# Meadowlark_Mini_Schematic_v30.net
KiCad netlist of a schematic drawn in EAGLE
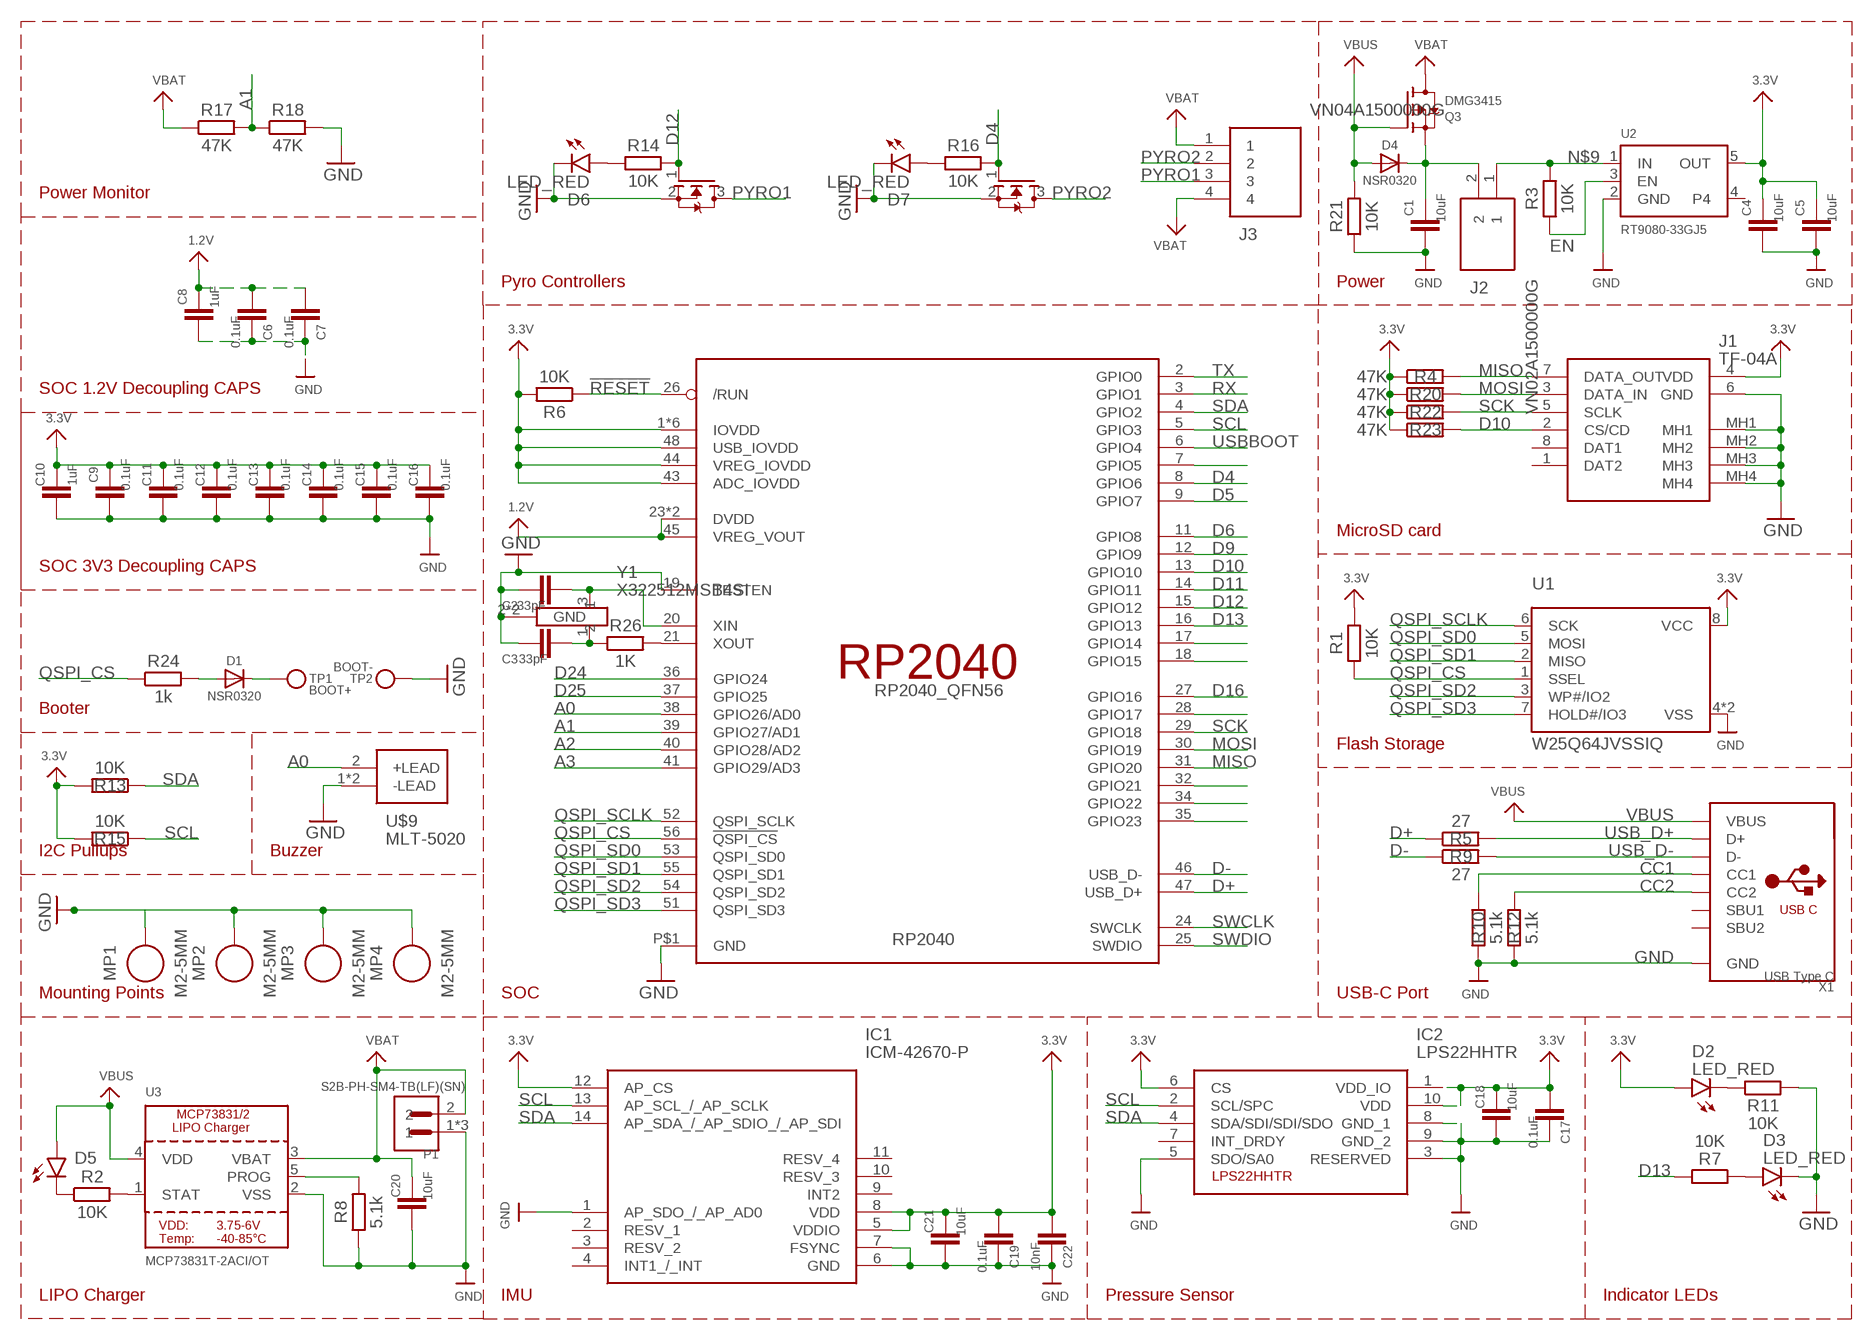
[diagram p0: schematic, sheet 1]

(export (version "E")
  (design (tool "Eeschema 10.0.6"))
  (components
    (comp (ref "C1")
      (value "10uF")
      (footprint "eagle-import:CAPC1005X60")
      (libsource (lib "eagle-import") (part "CCHIP-0402(1005-METRIC)_"))
    )
    (comp (ref "C2")
      (value "33pF")
      (footprint "eagle-import:CAPC1005X60")
      (libsource (lib "eagle-import") (part "CCHIP-0402(1005-METRIC)_"))
    )
    (comp (ref "C3")
      (value "33pF")
      (footprint "eagle-import:CAPC1005X60")
      (libsource (lib "eagle-import") (part "CCHIP-0402(1005-METRIC)_"))
    )
    (comp (ref "C4")
      (value "10uF")
      (footprint "eagle-import:CAPC1005X60")
      (libsource (lib "eagle-import") (part "CCHIP-0402(1005-METRIC)_"))
    )
    (comp (ref "C5")
      (value "10uF")
      (footprint "eagle-import:CAPC1005X60")
      (libsource (lib "eagle-import") (part "CCHIP-0402(1005-METRIC)_"))
    )
    (comp (ref "C6")
      (value "0.1uF")
      (footprint "eagle-import:CAPC1005X60")
      (libsource (lib "eagle-import") (part "CCHIP-0402(1005-METRIC)_"))
    )
    (comp (ref "C7")
      (value "0.1uF")
      (footprint "eagle-import:CAPC1005X60")
      (libsource (lib "eagle-import") (part "CCHIP-0402(1005-METRIC)_"))
    )
    (comp (ref "C8")
      (value "1uF")
      (footprint "eagle-import:CAPC1005X60")
      (libsource (lib "eagle-import") (part "CCHIP-0402(1005-METRIC)_"))
    )
    (comp (ref "C9")
      (value "0.1uF")
      (footprint "eagle-import:CAPC1005X60")
      (libsource (lib "eagle-import") (part "CCHIP-0402(1005-METRIC)_"))
    )
    (comp (ref "C10")
      (value "1uF")
      (footprint "eagle-import:CAPC1005X60")
      (libsource (lib "eagle-import") (part "CCHIP-0402(1005-METRIC)_"))
    )
    (comp (ref "C11")
      (value "0.1uF")
      (footprint "eagle-import:CAPC1005X60")
      (libsource (lib "eagle-import") (part "CCHIP-0402(1005-METRIC)_"))
    )
    (comp (ref "C12")
      (value "0.1uF")
      (footprint "eagle-import:CAPC1005X60")
      (libsource (lib "eagle-import") (part "CCHIP-0402(1005-METRIC)_"))
    )
    (comp (ref "C13")
      (value "0.1uF")
      (footprint "eagle-import:CAPC1005X60")
      (libsource (lib "eagle-import") (part "CCHIP-0402(1005-METRIC)_"))
    )
    (comp (ref "C14")
      (value "0.1uF")
      (footprint "eagle-import:CAPC1005X60")
      (libsource (lib "eagle-import") (part "CCHIP-0402(1005-METRIC)_"))
    )
    (comp (ref "C15")
      (value "0.1uF")
      (footprint "eagle-import:CAPC1005X60")
      (libsource (lib "eagle-import") (part "CCHIP-0402(1005-METRIC)_"))
    )
    (comp (ref "C16")
      (value "0.1uF")
      (footprint "eagle-import:CAPC1005X60")
      (libsource (lib "eagle-import") (part "CCHIP-0402(1005-METRIC)_"))
    )
    (comp (ref "C17")
      (value "0.1uF")
      (footprint "eagle-import:CAPC1005X60")
      (libsource (lib "eagle-import") (part "CCHIP-0402(1005-METRIC)_"))
    )
    (comp (ref "C18")
      (value "10uF")
      (footprint "eagle-import:CAPC1005X60")
      (libsource (lib "eagle-import") (part "CCHIP-0402(1005-METRIC)_"))
    )
    (comp (ref "C19")
      (value "0.1uF")
      (footprint "eagle-import:CAPC1005X60")
      (libsource (lib "eagle-import") (part "CCHIP-0402(1005-METRIC)_"))
    )
    (comp (ref "C20")
      (value "10uF")
      (footprint "eagle-import:CAPC1005X60")
      (libsource (lib "eagle-import") (part "CCHIP-0402(1005-METRIC)_"))
    )
    (comp (ref "C21")
      (value "10uF")
      (footprint "eagle-import:CAPC1005X60")
      (libsource (lib "eagle-import") (part "CCHIP-0402(1005-METRIC)_"))
    )
    (comp (ref "C22")
      (value "10nF")
      (footprint "eagle-import:CAPC1005X60")
      (libsource (lib "eagle-import") (part "CCHIP-0402(1005-METRIC)_"))
    )
    (comp (ref "D1")
      (value "NSR0320")
      (footprint "eagle-import:SOD-323_MINI")
      (libsource (lib "eagle-import") (part "DIODE_SOD323MINI"))
    )
    (comp (ref "D2")
      (value "LED_RED")
      (footprint "eagle-import:LEDC1608X55N_FLAT-R")
      (libsource (lib "eagle-import") (part "CHIP-FLAT-R_0603-0.55MM"))
    )
    (comp (ref "D3")
      (value "LED_RED")
      (footprint "eagle-import:LEDC1608X55N_FLAT-R")
      (libsource (lib "eagle-import") (part "CHIP-FLAT-R_0603-0.55MM"))
    )
    (comp (ref "D4")
      (value "NSR0320")
      (footprint "eagle-import:SOD-323_MINI")
      (libsource (lib "eagle-import") (part "DIODE_SOD323MINI"))
    )
    (comp (ref "D5")
      (value "LED_YELLOW")
      (footprint "eagle-import:LEDC1608X55N_FLAT-Y")
      (libsource (lib "eagle-import") (part "CHIP-FLAT-Y_0603-0.55MM"))
    )
    (comp (ref "D6")
      (value "LED_RED")
      (footprint "eagle-import:LEDC1608X55N_FLAT-R")
      (libsource (lib "eagle-import") (part "CHIP-FLAT-R_0603-0.55MM"))
    )
    (comp (ref "D7")
      (value "LED_RED")
      (footprint "eagle-import:LEDC1608X55N_FLAT-R")
      (libsource (lib "eagle-import") (part "CHIP-FLAT-R_0603-0.55MM"))
    )
    (comp (ref "IC1")
      (value "ICM-42670-P")
      (footprint "eagle-import:ICM42670P")
      (fields (field (name "MOUSER_PART_NUMBER") "410-ICM-42670-P"))
      (libsource (lib "eagle-import") (part "ICM-42670-P"))
    )
    (comp (ref "IC2")
      (value "LPS22HHTR")
      (footprint "eagle-import:LPS22HHTR")
      (fields (field (name "MOUSER_PART_NUMBER") "511-LPS22HHTR"))
      (libsource (lib "eagle-import") (part "LPS22HHTR"))
    )
    (comp (ref "J1")
      (value "TF-04A")
      (footprint "eagle-import:TF04A")
      (libsource (lib "eagle-import") (part "TF-04A"))
    )
    (comp (ref "J2")
      (value "VN02A1500000G")
      (footprint "eagle-import:VN02A1500000G")
      (fields (field (name "MOUSER_PART_NUMBER") "649-VN02A15000J0G"))
      (libsource (lib "eagle-import") (part "VN02A1500000G"))
    )
    (comp (ref "J3")
      (value "VN04A1500000G")
      (footprint "eagle-import:VN04A1500000G")
      (fields (field (name "MOUSER_PART_NUMBER") "649-VN04A15000J0G"))
      (libsource (lib "eagle-import") (part "VN04A1500000G"))
    )
    (comp (ref "MP1")
      (value "M2-5MM")
      (footprint "eagle-import:STANDOFF_HEX_MALE-FEMALE_400X500_M2X0.4_MTGP600H220")
      (libsource (lib "eagle-import") (part "STANDOFF_M/FM2_5MM_"))
    )
    (comp (ref "MP2")
      (value "M2-5MM")
      (footprint "eagle-import:STANDOFF_HEX_MALE-FEMALE_400X500_M2X0.4_MTGP600H220")
      (libsource (lib "eagle-import") (part "STANDOFF_M/FM2_5MM_"))
    )
    (comp (ref "MP3")
      (value "M2-5MM")
      (footprint "eagle-import:STANDOFF_HEX_MALE-FEMALE_400X500_M2X0.4_MTGP600H220")
      (libsource (lib "eagle-import") (part "STANDOFF_M/FM2_5MM_"))
    )
    (comp (ref "MP4")
      (value "M2-5MM")
      (footprint "eagle-import:STANDOFF_HEX_MALE-FEMALE_400X500_M2X0.4_MTGP600H220")
      (libsource (lib "eagle-import") (part "STANDOFF_M/FM2_5MM_"))
    )
    (comp (ref "P1")
      (value "S2B-PH-SM4-TB(LF)(SN)")
      (footprint "eagle-import:JST_S2B-PH-SM4-TB(LF)(SN)")
      (fields (field (name "MF") "JST Sales") (field (name "MP") "S2B-PH-SM4-TB (LF)(SN)"))
      (libsource (lib "eagle-import") (part "S2B-PH-SM4-TB(LF)(SN)"))
    )
    (comp (ref "Q1")
      (value "AO3400A")
      (footprint "eagle-import:SOT23-WIDE")
      (libsource (lib "eagle-import") (part "MOSFET-NWIDE"))
    )
    (comp (ref "Q2")
      (value "AO3400A")
      (footprint "eagle-import:SOT23-WIDE")
      (libsource (lib "eagle-import") (part "MOSFET-NWIDE"))
    )
    (comp (ref "Q3")
      (value "DMG3415")
      (footprint "eagle-import:SOT23-R")
      (libsource (lib "eagle-import") (part "MOSFET-P"))
    )
    (comp (ref "R1")
      (value "10K")
      (footprint "eagle-import:RESC1005X40")
      (libsource (lib "eagle-import") (part "RESISTOR_CHIP-0402(1005-METRIC)_"))
    )
    (comp (ref "R2")
      (value "10K")
      (footprint "eagle-import:RESC1005X40")
      (libsource (lib "eagle-import") (part "RESISTOR_CHIP-0402(1005-METRIC)_"))
    )
    (comp (ref "R3")
      (value "10K")
      (footprint "eagle-import:RESC1005X40")
      (libsource (lib "eagle-import") (part "RESISTOR_CHIP-0402(1005-METRIC)_"))
    )
    (comp (ref "R4")
      (value "47K")
      (footprint "eagle-import:RESC1005X40")
      (libsource (lib "eagle-import") (part "RESISTOR_CHIP-0402(1005-METRIC)_"))
    )
    (comp (ref "R5")
      (value "27")
      (footprint "eagle-import:RESC1005X40")
      (libsource (lib "eagle-import") (part "RESISTOR_CHIP-0402(1005-METRIC)_"))
    )
    (comp (ref "R6")
      (value "10K")
      (footprint "eagle-import:RESC1005X40")
      (libsource (lib "eagle-import") (part "RESISTOR_CHIP-0402(1005-METRIC)_"))
    )
    (comp (ref "R7")
      (value "10K")
      (footprint "eagle-import:RESC1005X40")
      (libsource (lib "eagle-import") (part "RESISTOR_CHIP-0402(1005-METRIC)_"))
    )
    (comp (ref "R8")
      (value "5.1k")
      (footprint "eagle-import:RESC1005X40")
      (libsource (lib "eagle-import") (part "RESISTOR_CHIP-0402(1005-METRIC)_"))
    )
    (comp (ref "R9")
      (value "27")
      (footprint "eagle-import:RESC1005X40")
      (libsource (lib "eagle-import") (part "RESISTOR_CHIP-0402(1005-METRIC)_"))
    )
    (comp (ref "R10")
      (value "5.1k")
      (footprint "eagle-import:RESC1005X40")
      (libsource (lib "eagle-import") (part "RESISTOR_CHIP-0402(1005-METRIC)_"))
    )
    (comp (ref "R11")
      (value "10K")
      (footprint "eagle-import:RESC1005X40")
      (libsource (lib "eagle-import") (part "RESISTOR_CHIP-0402(1005-METRIC)_"))
    )
    (comp (ref "R12")
      (value "5.1k")
      (footprint "eagle-import:RESC1005X40")
      (libsource (lib "eagle-import") (part "RESISTOR_CHIP-0402(1005-METRIC)_"))
    )
    (comp (ref "R13")
      (value "10K")
      (footprint "eagle-import:RESC1005X40")
      (libsource (lib "eagle-import") (part "RESISTOR_CHIP-0402(1005-METRIC)_"))
    )
    (comp (ref "R14")
      (value "10K")
      (footprint "eagle-import:RESC1005X40")
      (libsource (lib "eagle-import") (part "RESISTOR_CHIP-0402(1005-METRIC)_"))
    )
    (comp (ref "R15")
      (value "10K")
      (footprint "eagle-import:RESC1005X40")
      (libsource (lib "eagle-import") (part "RESISTOR_CHIP-0402(1005-METRIC)_"))
    )
    (comp (ref "R16")
      (value "10K")
      (footprint "eagle-import:RESC1005X40")
      (libsource (lib "eagle-import") (part "RESISTOR_CHIP-0402(1005-METRIC)_"))
    )
    (comp (ref "R17")
      (value "47K")
      (footprint "eagle-import:RESC1005X40")
      (libsource (lib "eagle-import") (part "RESISTOR_CHIP-0402(1005-METRIC)_"))
    )
    (comp (ref "R18")
      (value "47K")
      (footprint "eagle-import:RESC1005X40")
      (libsource (lib "eagle-import") (part "RESISTOR_CHIP-0402(1005-METRIC)_"))
    )
    (comp (ref "R20")
      (value "47K")
      (footprint "eagle-import:RESC1005X40")
      (libsource (lib "eagle-import") (part "RESISTOR_CHIP-0402(1005-METRIC)_"))
    )
    (comp (ref "R21")
      (value "10K")
      (footprint "eagle-import:RESC1005X40")
      (libsource (lib "eagle-import") (part "RESISTOR_CHIP-0402(1005-METRIC)_"))
    )
    (comp (ref "R22")
      (value "47K")
      (footprint "eagle-import:RESC1005X40")
      (libsource (lib "eagle-import") (part "RESISTOR_CHIP-0402(1005-METRIC)_"))
    )
    (comp (ref "R23")
      (value "47K")
      (footprint "eagle-import:RESC1005X40")
      (libsource (lib "eagle-import") (part "RESISTOR_CHIP-0402(1005-METRIC)_"))
    )
    (comp (ref "R24")
      (value "1k")
      (footprint "eagle-import:RESC1005X40")
      (libsource (lib "eagle-import") (part "RCHIP-0402(1005-METRIC)_"))
    )
    (comp (ref "R26")
      (value "1K")
      (footprint "eagle-import:RESC1005X40")
      (libsource (lib "eagle-import") (part "RESISTOR_CHIP-0402(1005-METRIC)_"))
    )
    (comp (ref "RP2040")
      (value "RP2040_QFN56")
      (footprint "eagle-import:QFN56_7MM_REDUCEDEPAD")
      (libsource (lib "eagle-import") (part "RP2040_QFN56"))
    )
    (comp (ref "TP1")
      (value "BOOT+")
      (footprint "eagle-import:TESTPOINT_ROUND_1.5MM_NO")
      (libsource (lib "eagle-import") (part "TESTPOINTROUND1.5MMNO"))
    )
    (comp (ref "TP2")
      (value "BOOT-")
      (footprint "eagle-import:TESTPOINT_ROUND_1.5MM_NO")
      (libsource (lib "eagle-import") (part "TESTPOINTROUND1.5MMNO"))
    )
    (comp (ref "U$9")
      (value "MLT-5020")
      (footprint "eagle-import:MLT5020")
      (libsource (lib "eagle-import") (part "MLT-5020"))
    )
    (comp (ref "U1")
      (value "W25Q64JVSSIQ")
      (footprint "eagle-import:USON8_4X4")
      (libsource (lib "eagle-import") (part "SPIFLASH_8PIN_4X4"))
    )
    (comp (ref "U2")
      (value "RT9080-33GJ5")
      (footprint "eagle-import:SOT23-5")
      (fields (field (name "JLC_ROTATION") "0"))
      (libsource (lib "eagle-import") (part "VREG_SOT23-5"))
    )
    (comp (ref "U3")
      (value "MCP73831T-2ACI/OT")
      (footprint "eagle-import:SOT23-5")
      (libsource (lib "eagle-import") (part "MCP73831/2"))
    )
    (comp (ref "X1")
      (value "USB Type C")
      (footprint "eagle-import:USB_C_CUSB31-CFM2AX-01-X")
      (libsource (lib "eagle-import") (part "USB_C"))
    )
    (comp (ref "Y1")
      (value "X322512MSB4SI")
      (footprint "eagle-import:X322512MSB4SI")
      (libsource (lib "eagle-import") (part "X322512MSB4SI"))
    )
  )
  (nets
    (net (code "1") (name "/A0") (class "Default")
      (node (ref "RP2040") (pin "38") (pinfunction "GPIO26/AD0_38") (pintype "bidirectional"))
      (node (ref "U$9") (pin "2") (pinfunction "+LEAD_2") (pintype "bidirectional"))
    )
    (net (code "2") (name "/A1") (class "Default")
      (node (ref "R17") (pin "2") (pinfunction "2_2") (pintype "passive"))
      (node (ref "R18") (pin "1") (pinfunction "1_1") (pintype "passive"))
      (node (ref "RP2040") (pin "39") (pinfunction "GPIO27/AD1_39") (pintype "bidirectional"))
    )
    (net (code "3") (name "/A2") (class "Default")
      (node (ref "RP2040") (pin "40") (pinfunction "GPIO28/AD2_40") (pintype "bidirectional"))
    )
    (net (code "4") (name "/A3") (class "Default")
      (node (ref "RP2040") (pin "41") (pinfunction "GPIO29/AD3_41") (pintype "bidirectional"))
    )
    (net (code "5") (name "/CC1") (class "Default")
      (node (ref "R10") (pin "2") (pinfunction "2_2") (pintype "passive"))
      (node (ref "X1") (pin "A5") (pinfunction "CC1_A5") (pintype "bidirectional"))
    )
    (net (code "6") (name "/CC2") (class "Default")
      (node (ref "R12") (pin "2") (pinfunction "2_2") (pintype "passive"))
      (node (ref "X1") (pin "B5") (pinfunction "CC2_B5") (pintype "bidirectional"))
    )
    (net (code "7") (name "/D+") (class "Default")
      (node (ref "R5") (pin "1") (pinfunction "1_1") (pintype "passive"))
      (node (ref "RP2040") (pin "47") (pinfunction "USB_D+_47") (pintype "bidirectional"))
    )
    (net (code "8") (name "/D-") (class "Default")
      (node (ref "R9") (pin "1") (pinfunction "1_1") (pintype "passive"))
      (node (ref "RP2040") (pin "46") (pinfunction "USB_D-_46") (pintype "bidirectional"))
    )
    (net (code "9") (name "/D4") (class "Default")
      (node (ref "Q2") (pin "1") (pinfunction "G_1") (pintype "bidirectional"))
      (node (ref "R16") (pin "2") (pinfunction "2_2") (pintype "passive"))
      (node (ref "RP2040") (pin "8") (pinfunction "GPIO6_8") (pintype "bidirectional"))
    )
    (net (code "10") (name "/D5") (class "Default")
      (node (ref "RP2040") (pin "9") (pinfunction "GPIO7_9") (pintype "bidirectional"))
    )
    (net (code "11") (name "/D6") (class "Default")
      (node (ref "RP2040") (pin "11") (pinfunction "GPIO8_11") (pintype "bidirectional"))
    )
    (net (code "12") (name "/D9") (class "Default")
      (node (ref "RP2040") (pin "12") (pinfunction "GPIO9_12") (pintype "bidirectional"))
    )
    (net (code "13") (name "/D10") (class "Default")
      (node (ref "J1") (pin "2") (pinfunction "CS/CD_2") (pintype "bidirectional"))
      (node (ref "R23") (pin "2") (pinfunction "2_2") (pintype "passive"))
      (node (ref "RP2040") (pin "13") (pinfunction "GPIO10_13") (pintype "bidirectional"))
    )
    (net (code "14") (name "/D11") (class "Default")
      (node (ref "RP2040") (pin "14") (pinfunction "GPIO11_14") (pintype "bidirectional"))
    )
    (net (code "15") (name "/D12") (class "Default")
      (node (ref "Q1") (pin "1") (pinfunction "G_1") (pintype "bidirectional"))
      (node (ref "R14") (pin "2") (pinfunction "2_2") (pintype "passive"))
      (node (ref "RP2040") (pin "15") (pinfunction "GPIO12_15") (pintype "bidirectional"))
    )
    (net (code "16") (name "/D13") (class "Default")
      (node (ref "R7") (pin "2") (pinfunction "2_2") (pintype "passive"))
      (node (ref "RP2040") (pin "16") (pinfunction "GPIO13_16") (pintype "bidirectional"))
    )
    (net (code "17") (name "/D16") (class "Default")
      (node (ref "RP2040") (pin "27") (pinfunction "GPIO16_27") (pintype "bidirectional"))
    )
    (net (code "18") (name "/D24") (class "Default")
      (node (ref "RP2040") (pin "36") (pinfunction "GPIO24_36") (pintype "bidirectional"))
    )
    (net (code "19") (name "/D25") (class "Default")
      (node (ref "RP2040") (pin "37") (pinfunction "GPIO25_37") (pintype "bidirectional"))
    )
    (net (code "20") (name "/EN") (class "Default")
      (node (ref "R3") (pin "1") (pinfunction "1_1") (pintype "passive"))
      (node (ref "U2") (pin "3") (pinfunction "EN_3") (pintype "input"))
    )
    (net (code "21") (name "/MISO") (class "Default")
      (node (ref "J1") (pin "7") (pinfunction "DATA_OUT_7") (pintype "bidirectional"))
      (node (ref "R4") (pin "2") (pinfunction "2_2") (pintype "passive"))
      (node (ref "RP2040") (pin "31") (pinfunction "GPIO20_31") (pintype "bidirectional"))
    )
    (net (code "22") (name "/MOSI") (class "Default")
      (node (ref "J1") (pin "3") (pinfunction "DATA_IN_3") (pintype "bidirectional"))
      (node (ref "R20") (pin "2") (pinfunction "2_2") (pintype "passive"))
      (node (ref "RP2040") (pin "30") (pinfunction "GPIO19_30") (pintype "bidirectional"))
    )
    (net (code "23") (name "/N$9") (class "Default")
      (node (ref "J2") (pin "1") (pinfunction "1_1") (pintype "bidirectional"))
      (node (ref "R3") (pin "2") (pinfunction "2_2") (pintype "passive"))
      (node (ref "U2") (pin "1") (pinfunction "IN_1") (pintype "power_in"))
    )
    (net (code "24") (name "/PYRO1") (class "Default")
      (node (ref "J3") (pin "3") (pinfunction "3_3") (pintype "bidirectional"))
      (node (ref "Q1") (pin "3") (pinfunction "D_3") (pintype "bidirectional"))
    )
    (net (code "25") (name "/PYRO2") (class "Default")
      (node (ref "J3") (pin "2") (pinfunction "2_2") (pintype "bidirectional"))
      (node (ref "Q2") (pin "3") (pinfunction "D_3") (pintype "bidirectional"))
    )
    (net (code "26") (name "/QSPI_CS") (class "Default")
      (node (ref "R1") (pin "1") (pinfunction "1_1") (pintype "passive"))
      (node (ref "R24") (pin "1") (pinfunction "1_1") (pintype "passive"))
      (node (ref "RP2040") (pin "56") (pinfunction "~{QSPI_CS}_56") (pintype "bidirectional"))
      (node (ref "U1") (pin "1") (pinfunction "SSEL_1") (pintype "bidirectional"))
    )
    (net (code "27") (name "/QSPI_SCLK") (class "Default")
      (node (ref "RP2040") (pin "52") (pinfunction "QSPI_SCLK_52") (pintype "bidirectional"))
      (node (ref "U1") (pin "6") (pinfunction "SCK_6") (pintype "bidirectional"))
    )
    (net (code "28") (name "/QSPI_SD0") (class "Default")
      (node (ref "RP2040") (pin "53") (pinfunction "QSPI_SD0_53") (pintype "bidirectional"))
      (node (ref "U1") (pin "5") (pinfunction "MOSI_5") (pintype "bidirectional"))
    )
    (net (code "29") (name "/QSPI_SD1") (class "Default")
      (node (ref "RP2040") (pin "55") (pinfunction "QSPI_SD1_55") (pintype "bidirectional"))
      (node (ref "U1") (pin "2") (pinfunction "MISO_2") (pintype "bidirectional"))
    )
    (net (code "30") (name "/QSPI_SD2") (class "Default")
      (node (ref "RP2040") (pin "54") (pinfunction "QSPI_SD2_54") (pintype "bidirectional"))
      (node (ref "U1") (pin "3") (pinfunction "WP#/IO2_3") (pintype "bidirectional"))
    )
    (net (code "31") (name "/QSPI_SD3") (class "Default")
      (node (ref "RP2040") (pin "51") (pinfunction "QSPI_SD3_51") (pintype "bidirectional"))
      (node (ref "U1") (pin "7") (pinfunction "HOLD#/IO3_7") (pintype "bidirectional"))
    )
    (net (code "32") (name "/RX") (class "Default")
      (node (ref "RP2040") (pin "3") (pinfunction "GPIO1_3") (pintype "bidirectional"))
    )
    (net (code "33") (name "/SCK") (class "Default")
      (node (ref "J1") (pin "5") (pinfunction "SCLK_5") (pintype "bidirectional"))
      (node (ref "R22") (pin "2") (pinfunction "2_2") (pintype "passive"))
      (node (ref "RP2040") (pin "29") (pinfunction "GPIO18_29") (pintype "bidirectional"))
    )
    (net (code "34") (name "/SCL") (class "Default")
      (node (ref "IC1") (pin "13") (pinfunction "AP_SCL_/_AP_SCLK_13") (pintype "bidirectional"))
      (node (ref "IC2") (pin "2") (pinfunction "SCL/SPC_2") (pintype "bidirectional"))
      (node (ref "R15") (pin "1") (pinfunction "1_1") (pintype "passive"))
      (node (ref "RP2040") (pin "5") (pinfunction "GPIO3_5") (pintype "bidirectional"))
    )
    (net (code "35") (name "/SDA") (class "Default")
      (node (ref "IC1") (pin "14") (pinfunction "AP_SDA_/_AP_SDIO_/_AP_SDI_14") (pintype "bidirectional"))
      (node (ref "IC2") (pin "4") (pinfunction "SDA/SDI/SDI/SDO_4") (pintype "bidirectional"))
      (node (ref "R13") (pin "1") (pinfunction "1_1") (pintype "passive"))
      (node (ref "RP2040") (pin "4") (pinfunction "GPIO2_4") (pintype "bidirectional"))
    )
    (net (code "36") (name "/SWCLK") (class "Default")
      (node (ref "RP2040") (pin "24") (pinfunction "SWCLK_24") (pintype "bidirectional"))
    )
    (net (code "37") (name "/SWDIO") (class "Default")
      (node (ref "RP2040") (pin "25") (pinfunction "SWDIO_25") (pintype "bidirectional"))
    )
    (net (code "38") (name "/TX") (class "Default")
      (node (ref "RP2040") (pin "2") (pinfunction "GPIO0_2") (pintype "bidirectional"))
    )
    (net (code "39") (name "/USBBOOT") (class "Default")
      (node (ref "D1") (pin "C") (pinfunction "C_C") (pintype "passive"))
      (node (ref "RP2040") (pin "6") (pinfunction "GPIO4_6") (pintype "bidirectional"))
      (node (ref "TP1") (pin "P$1") (pinfunction "P$1_P$1") (pintype "bidirectional"))
    )
    (net (code "40") (name "/USB_D+") (class "Default")
      (node (ref "R5") (pin "2") (pinfunction "2_2") (pintype "passive"))
      (node (ref "X1") (pin "A6") (pinfunction "D+_A6") (pintype "bidirectional"))
      (node (ref "X1") (pin "B6") (pinfunction "D+_B6") (pintype "bidirectional"))
    )
    (net (code "41") (name "/USB_D-") (class "Default")
      (node (ref "R9") (pin "2") (pinfunction "2_2") (pintype "passive"))
      (node (ref "X1") (pin "A7") (pinfunction "D-_A7") (pintype "bidirectional"))
      (node (ref "X1") (pin "B7") (pinfunction "D-_B7") (pintype "bidirectional"))
    )
    (net (code "42") (name "/~{RESET}") (class "Default")
      (node (ref "R6") (pin "1") (pinfunction "1_1") (pintype "passive"))
      (node (ref "RP2040") (pin "26") (pinfunction "/RUN_26") (pintype "bidirectional"))
    )
    (net (code "43") (name "1.2V") (class "Default")
      (node (ref "C6") (pin "2") (pinfunction "2_2") (pintype "passive"))
      (node (ref "C7") (pin "2") (pinfunction "2_2") (pintype "passive"))
      (node (ref "C8") (pin "1") (pinfunction "1_1") (pintype "passive"))
      (node (ref "RP2040") (pin "23") (pinfunction "DVDD_23") (pintype "power_in"))
      (node (ref "RP2040") (pin "45") (pinfunction "VREG_VOUT_45") (pintype "power_in"))
      (node (ref "RP2040") (pin "50") (pinfunction "DVDD_50") (pintype "power_in"))
    )
    (net (code "44") (name "3.3V") (class "Default")
      (node (ref "C10") (pin "1") (pinfunction "1_1") (pintype "passive"))
      (node (ref "C11") (pin "1") (pinfunction "1_1") (pintype "passive"))
      (node (ref "C12") (pin "1") (pinfunction "1_1") (pintype "passive"))
      (node (ref "C13") (pin "1") (pinfunction "1_1") (pintype "passive"))
      (node (ref "C14") (pin "1") (pinfunction "1_1") (pintype "passive"))
      (node (ref "C15") (pin "1") (pinfunction "1_1") (pintype "passive"))
      (node (ref "C16") (pin "1") (pinfunction "1_1") (pintype "passive"))
      (node (ref "C17") (pin "2") (pinfunction "2_2") (pintype "passive"))
      (node (ref "C18") (pin "1") (pinfunction "1_1") (pintype "passive"))
      (node (ref "C19") (pin "2") (pinfunction "2_2") (pintype "passive"))
      (node (ref "C21") (pin "1") (pinfunction "1_1") (pintype "passive"))
      (node (ref "C22") (pin "2") (pinfunction "2_2") (pintype "passive"))
      (node (ref "C4") (pin "1") (pinfunction "1_1") (pintype "passive"))
      (node (ref "C5") (pin "1") (pinfunction "1_1") (pintype "passive"))
      (node (ref "C9") (pin "1") (pinfunction "1_1") (pintype "passive"))
      (node (ref "D2") (pin "A") (pinfunction "A_A") (pintype "passive"))
      (node (ref "IC1") (pin "12") (pinfunction "AP_CS_12") (pintype "bidirectional"))
      (node (ref "IC1") (pin "5") (pinfunction "VDDIO_5") (pintype "bidirectional"))
      (node (ref "IC1") (pin "8") (pinfunction "VDD_8") (pintype "bidirectional"))
      (node (ref "IC2") (pin "1") (pinfunction "VDD_IO_1") (pintype "bidirectional"))
      (node (ref "IC2") (pin "10") (pinfunction "VDD_10") (pintype "bidirectional"))
      (node (ref "IC2") (pin "6") (pinfunction "CS_6") (pintype "bidirectional"))
      (node (ref "J1") (pin "4") (pinfunction "VDD_4") (pintype "bidirectional"))
      (node (ref "R1") (pin "2") (pinfunction "2_2") (pintype "passive"))
      (node (ref "R13") (pin "2") (pinfunction "2_2") (pintype "passive"))
      (node (ref "R15") (pin "2") (pinfunction "2_2") (pintype "passive"))
      (node (ref "R20") (pin "1") (pinfunction "1_1") (pintype "passive"))
      (node (ref "R22") (pin "1") (pinfunction "1_1") (pintype "passive"))
      (node (ref "R23") (pin "1") (pinfunction "1_1") (pintype "passive"))
      (node (ref "R4") (pin "1") (pinfunction "1_1") (pintype "passive"))
      (node (ref "R6") (pin "2") (pinfunction "2_2") (pintype "passive"))
      (node (ref "RP2040") (pin "1") (pinfunction "IOVDD_1") (pintype "power_in"))
      (node (ref "RP2040") (pin "10") (pinfunction "IOVDD_10") (pintype "power_in"))
      (node (ref "RP2040") (pin "22") (pinfunction "IOVDD_22") (pintype "power_in"))
      (node (ref "RP2040") (pin "33") (pinfunction "IOVDD_33") (pintype "power_in"))
      (node (ref "RP2040") (pin "42") (pinfunction "IOVDD_42") (pintype "power_in"))
      (node (ref "RP2040") (pin "43") (pinfunction "ADC_IOVDD_43") (pintype "power_in"))
      (node (ref "RP2040") (pin "44") (pinfunction "VREG_IOVDD_44") (pintype "power_in"))
      (node (ref "RP2040") (pin "48") (pinfunction "USB_IOVDD_48") (pintype "power_in"))
      (node (ref "RP2040") (pin "49") (pinfunction "IOVDD_49") (pintype "power_in"))
      (node (ref "U1") (pin "8") (pinfunction "VCC_8") (pintype "bidirectional"))
      (node (ref "U2") (pin "5") (pinfunction "OUT_5") (pintype "power_in"))
    )
    (net (code "45") (name "GND") (class "Default")
      (node (ref "C1") (pin "2") (pinfunction "2_2") (pintype "passive"))
      (node (ref "C10") (pin "2") (pinfunction "2_2") (pintype "passive"))
      (node (ref "C11") (pin "2") (pinfunction "2_2") (pintype "passive"))
      (node (ref "C12") (pin "2") (pinfunction "2_2") (pintype "passive"))
      (node (ref "C13") (pin "2") (pinfunction "2_2") (pintype "passive"))
      (node (ref "C14") (pin "2") (pinfunction "2_2") (pintype "passive"))
      (node (ref "C15") (pin "2") (pinfunction "2_2") (pintype "passive"))
      (node (ref "C16") (pin "2") (pinfunction "2_2") (pintype "passive"))
      (node (ref "C17") (pin "1") (pinfunction "1_1") (pintype "passive"))
      (node (ref "C18") (pin "2") (pinfunction "2_2") (pintype "passive"))
      (node (ref "C19") (pin "1") (pinfunction "1_1") (pintype "passive"))
      (node (ref "C2") (pin "1") (pinfunction "1_1") (pintype "passive"))
      (node (ref "C20") (pin "2") (pinfunction "2_2") (pintype "passive"))
      (node (ref "C21") (pin "2") (pinfunction "2_2") (pintype "passive"))
      (node (ref "C22") (pin "1") (pinfunction "1_1") (pintype "passive"))
      (node (ref "C3") (pin "1") (pinfunction "1_1") (pintype "passive"))
      (node (ref "C4") (pin "2") (pinfunction "2_2") (pintype "passive"))
      (node (ref "C5") (pin "2") (pinfunction "2_2") (pintype "passive"))
      (node (ref "C6") (pin "1") (pinfunction "1_1") (pintype "passive"))
      (node (ref "C7") (pin "1") (pinfunction "1_1") (pintype "passive"))
      (node (ref "C8") (pin "2") (pinfunction "2_2") (pintype "passive"))
      (node (ref "C9") (pin "2") (pinfunction "2_2") (pintype "passive"))
      (node (ref "D3") (pin "C") (pinfunction "C_C") (pintype "passive"))
      (node (ref "D6") (pin "C") (pinfunction "C_C") (pintype "passive"))
      (node (ref "D7") (pin "C") (pinfunction "C_C") (pintype "passive"))
      (node (ref "IC1") (pin "1") (pinfunction "AP_SDO_/_AP_AD0_1") (pintype "bidirectional"))
      (node (ref "IC1") (pin "6") (pinfunction "GND_6") (pintype "bidirectional"))
      (node (ref "IC1") (pin "7") (pinfunction "FSYNC_7") (pintype "bidirectional"))
      (node (ref "IC2") (pin "3") (pinfunction "RESERVED_3") (pintype "bidirectional"))
      (node (ref "IC2") (pin "5") (pinfunction "SDO/SA0_5") (pintype "bidirectional"))
      (node (ref "IC2") (pin "8") (pinfunction "GND_1_8") (pintype "bidirectional"))
      (node (ref "IC2") (pin "9") (pinfunction "GND_2_9") (pintype "bidirectional"))
      (node (ref "J1") (pin "6") (pinfunction "GND_6") (pintype "bidirectional"))
      (node (ref "J1") (pin "MH1") (pinfunction "MH1_MH1") (pintype "bidirectional"))
      (node (ref "J1") (pin "MH2") (pinfunction "MH2_MH2") (pintype "bidirectional"))
      (node (ref "J1") (pin "MH3") (pinfunction "MH3_MH3") (pintype "bidirectional"))
      (node (ref "J1") (pin "MH4") (pinfunction "MH4_MH4") (pintype "bidirectional"))
      (node (ref "MP1") (pin "1") (pinfunction "P$1_1") (pintype "passive"))
      (node (ref "MP2") (pin "1") (pinfunction "P$1_1") (pintype "passive"))
      (node (ref "MP3") (pin "1") (pinfunction "P$1_1") (pintype "passive"))
      (node (ref "MP4") (pin "1") (pinfunction "P$1_1") (pintype "passive"))
      (node (ref "P1") (pin "1") (pinfunction "1_1") (pintype "passive"))
      (node (ref "P1") (pin "P1") (pinfunction "1_P1") (pintype "passive"))
      (node (ref "P1") (pin "P2") (pinfunction "1_P2") (pintype "passive"))
      (node (ref "Q1") (pin "2") (pinfunction "S_2") (pintype "bidirectional"))
      (node (ref "Q2") (pin "2") (pinfunction "S_2") (pintype "bidirectional"))
      (node (ref "R10") (pin "1") (pinfunction "1_1") (pintype "passive"))
      (node (ref "R11") (pin "2") (pinfunction "2_2") (pintype "passive"))
      (node (ref "R12") (pin "1") (pinfunction "1_1") (pintype "passive"))
      (node (ref "R18") (pin "2") (pinfunction "2_2") (pintype "passive"))
      (node (ref "R21") (pin "1") (pinfunction "1_1") (pintype "passive"))
      (node (ref "R8") (pin "1") (pinfunction "1_1") (pintype "passive"))
      (node (ref "RP2040") (pin "19") (pinfunction "TESTEN_19") (pintype "input"))
      (node (ref "RP2040") (pin "P$1") (pinfunction "GND_P$1") (pintype "power_in"))
      (node (ref "TP2") (pin "P$1") (pinfunction "P$1_P$1") (pintype "bidirectional"))
      (node (ref "U$9") (pin "1") (pinfunction "-LEAD_1") (pintype "bidirectional"))
      (node (ref "U$9") (pin "3") (pinfunction "-LEAD_3") (pintype "bidirectional"))
      (node (ref "U1") (pin "4") (pinfunction "VSS_4") (pintype "bidirectional"))
      (node (ref "U1") (pin "PAD") (pinfunction "VSS_PAD") (pintype "bidirectional"))
      (node (ref "U2") (pin "2") (pinfunction "GND_2") (pintype "power_in"))
      (node (ref "U3") (pin "2") (pinfunction "VSS_2") (pintype "power_in"))
      (node (ref "X1") (pin "A1B12") (pinfunction "GND_A1B12") (pintype "power_in"))
      (node (ref "X1") (pin "B1A12") (pinfunction "GND_B1A12") (pintype "power_in"))
      (node (ref "Y1") (pin "2") (pinfunction "GND_2") (pintype "bidirectional"))
      (node (ref "Y1") (pin "4") (pinfunction "GND_4") (pintype "bidirectional"))
    )
    (net (code "46") (name "Net-(C3-Pad2)") (class "Default")
      (node (ref "C3") (pin "2") (pinfunction "2_2") (pintype "passive"))
      (node (ref "R26") (pin "1") (pinfunction "1_1") (pintype "passive"))
      (node (ref "Y1") (pin "1") (pinfunction "1_1") (pintype "bidirectional"))
    )
    (net (code "47") (name "Net-(D1-PadA)") (class "Default")
      (node (ref "D1") (pin "A") (pinfunction "A_A") (pintype "passive"))
      (node (ref "R24") (pin "2") (pinfunction "2_2") (pintype "passive"))
    )
    (net (code "48") (name "Net-(D2-PadC)") (class "Default")
      (node (ref "D2") (pin "C") (pinfunction "C_C") (pintype "passive"))
      (node (ref "R11") (pin "1") (pinfunction "1_1") (pintype "passive"))
    )
    (net (code "49") (name "Net-(D3-PadA)") (class "Default")
      (node (ref "D3") (pin "A") (pinfunction "A_A") (pintype "passive"))
      (node (ref "R7") (pin "1") (pinfunction "1_1") (pintype "passive"))
    )
    (net (code "50") (name "Net-(D5-PadC)") (class "Default")
      (node (ref "D5") (pin "C") (pinfunction "C_C") (pintype "passive"))
      (node (ref "R2") (pin "1") (pinfunction "1_1") (pintype "passive"))
    )
    (net (code "51") (name "Net-(D6-PadA)") (class "Default")
      (node (ref "D6") (pin "A") (pinfunction "A_A") (pintype "passive"))
      (node (ref "R14") (pin "1") (pinfunction "1_1") (pintype "passive"))
    )
    (net (code "52") (name "Net-(D7-PadA)") (class "Default")
      (node (ref "D7") (pin "A") (pinfunction "A_A") (pintype "passive"))
      (node (ref "R16") (pin "1") (pinfunction "1_1") (pintype "passive"))
    )
    (net (code "53") (name "Net-(Q3-S)") (class "Default")
      (node (ref "C1") (pin "1") (pinfunction "1_1") (pintype "passive"))
      (node (ref "D4") (pin "C") (pinfunction "C_C") (pintype "passive"))
      (node (ref "J2") (pin "2") (pinfunction "2_2") (pintype "bidirectional"))
      (node (ref "Q3") (pin "2") (pinfunction "S_2") (pintype "passive"))
    )
    (net (code "54") (name "Net-(RP2040-XIN)") (class "Default")
      (node (ref "C2") (pin "2") (pinfunction "2_2") (pintype "passive"))
      (node (ref "RP2040") (pin "20") (pinfunction "XIN_20") (pintype "input"))
      (node (ref "Y1") (pin "3") (pinfunction "2_3") (pintype "bidirectional"))
    )
    (net (code "55") (name "Net-(RP2040-XOUT)") (class "Default")
      (node (ref "R26") (pin "2") (pinfunction "2_2") (pintype "passive"))
      (node (ref "RP2040") (pin "21") (pinfunction "XOUT_21") (pintype "output"))
    )
    (net (code "56") (name "Net-(U3-PROG)") (class "Default")
      (node (ref "R8") (pin "2") (pinfunction "2_2") (pintype "passive"))
      (node (ref "U3") (pin "5") (pinfunction "PROG_5") (pintype "input"))
    )
    (net (code "57") (name "Net-(U3-STAT)") (class "Default")
      (node (ref "R2") (pin "2") (pinfunction "2_2") (pintype "passive"))
      (node (ref "U3") (pin "1") (pinfunction "STAT_1") (pintype "output"))
    )
    (net (code "58") (name "VBAT") (class "Default")
      (node (ref "C20") (pin "1") (pinfunction "1_1") (pintype "passive"))
      (node (ref "J3") (pin "1") (pinfunction "1_1") (pintype "bidirectional"))
      (node (ref "J3") (pin "4") (pinfunction "4_4") (pintype "bidirectional"))
      (node (ref "P1") (pin "2") (pinfunction "2_2") (pintype "passive"))
      (node (ref "Q3") (pin "3") (pinfunction "D_3") (pintype "passive"))
      (node (ref "R17") (pin "1") (pinfunction "1_1") (pintype "passive"))
      (node (ref "U3") (pin "3") (pinfunction "VBAT_3") (pintype "power_in"))
    )
    (net (code "59") (name "VBUS") (class "Default")
      (node (ref "D4") (pin "A") (pinfunction "A_A") (pintype "passive"))
      (node (ref "D5") (pin "A") (pinfunction "A_A") (pintype "passive"))
      (node (ref "Q3") (pin "1") (pinfunction "G_1") (pintype "passive"))
      (node (ref "R21") (pin "2") (pinfunction "2_2") (pintype "passive"))
      (node (ref "U3") (pin "4") (pinfunction "VDD_4") (pintype "power_in"))
      (node (ref "X1") (pin "A4B9") (pinfunction "VBUS_A4B9") (pintype "power_in"))
      (node (ref "X1") (pin "B4A9") (pinfunction "VBUS_B4A9") (pintype "power_in"))
    )
    (net (code "60") (name "unconnected-(IC1-INT1_{slash}_INT-Pad4)") (class "Default")
      (node (ref "IC1") (pin "4") (pinfunction "INT1_/_INT_4") (pintype "bidirectional"))
    )
    (net (code "61") (name "unconnected-(IC1-INT2-Pad9)") (class "Default")
      (node (ref "IC1") (pin "9") (pinfunction "INT2_9") (pintype "bidirectional"))
    )
    (net (code "62") (name "unconnected-(IC1-RESV_1-Pad2)") (class "Default")
      (node (ref "IC1") (pin "2") (pinfunction "RESV_1_2") (pintype "bidirectional"))
    )
    (net (code "63") (name "unconnected-(IC1-RESV_2-Pad3)") (class "Default")
      (node (ref "IC1") (pin "3") (pinfunction "RESV_2_3") (pintype "bidirectional"))
    )
    (net (code "64") (name "unconnected-(IC1-RESV_3-Pad10)") (class "Default")
      (node (ref "IC1") (pin "10") (pinfunction "RESV_3_10") (pintype "bidirectional"))
    )
    (net (code "65") (name "unconnected-(IC1-RESV_4-Pad11)") (class "Default")
      (node (ref "IC1") (pin "11") (pinfunction "RESV_4_11") (pintype "bidirectional"))
    )
    (net (code "66") (name "unconnected-(IC2-INT_DRDY-Pad7)") (class "Default")
      (node (ref "IC2") (pin "7") (pinfunction "INT_DRDY_7") (pintype "bidirectional"))
    )
    (net (code "67") (name "unconnected-(J1-DAT1-Pad8)") (class "Default")
      (node (ref "J1") (pin "8") (pinfunction "DAT1_8") (pintype "bidirectional"))
    )
    (net (code "68") (name "unconnected-(J1-DAT2-Pad1)") (class "Default")
      (node (ref "J1") (pin "1") (pinfunction "DAT2_1") (pintype "bidirectional"))
    )
    (net (code "69") (name "unconnected-(RP2040-GPIO5-Pad7)") (class "Default")
      (node (ref "RP2040") (pin "7") (pinfunction "GPIO5_7") (pintype "bidirectional"))
    )
    (net (code "70") (name "unconnected-(RP2040-GPIO14-Pad17)") (class "Default")
      (node (ref "RP2040") (pin "17") (pinfunction "GPIO14_17") (pintype "bidirectional"))
    )
    (net (code "71") (name "unconnected-(RP2040-GPIO15-Pad18)") (class "Default")
      (node (ref "RP2040") (pin "18") (pinfunction "GPIO15_18") (pintype "bidirectional"))
    )
    (net (code "72") (name "unconnected-(RP2040-GPIO17-Pad28)") (class "Default")
      (node (ref "RP2040") (pin "28") (pinfunction "GPIO17_28") (pintype "bidirectional"))
    )
    (net (code "73") (name "unconnected-(RP2040-GPIO21-Pad32)") (class "Default")
      (node (ref "RP2040") (pin "32") (pinfunction "GPIO21_32") (pintype "bidirectional"))
    )
    (net (code "74") (name "unconnected-(RP2040-GPIO22-Pad34)") (class "Default")
      (node (ref "RP2040") (pin "34") (pinfunction "GPIO22_34") (pintype "bidirectional"))
    )
    (net (code "75") (name "unconnected-(RP2040-GPIO23-Pad35)") (class "Default")
      (node (ref "RP2040") (pin "35") (pinfunction "GPIO23_35") (pintype "bidirectional"))
    )
    (net (code "76") (name "unconnected-(U2-P4-Pad4)") (class "Default")
      (node (ref "U2") (pin "4") (pinfunction "P4_4") (pintype "bidirectional"))
    )
    (net (code "77") (name "unconnected-(X1-SBU1-PadA8)") (class "Default")
      (node (ref "X1") (pin "A8") (pinfunction "SBU1_A8") (pintype "bidirectional"))
    )
    (net (code "78") (name "unconnected-(X1-SBU2-PadB8)") (class "Default")
      (node (ref "X1") (pin "B8") (pinfunction "SBU2_B8") (pintype "bidirectional"))
    )
  )
)
